# LoadBoard.net
KiCad netlist of a schematic drawn in EAGLE
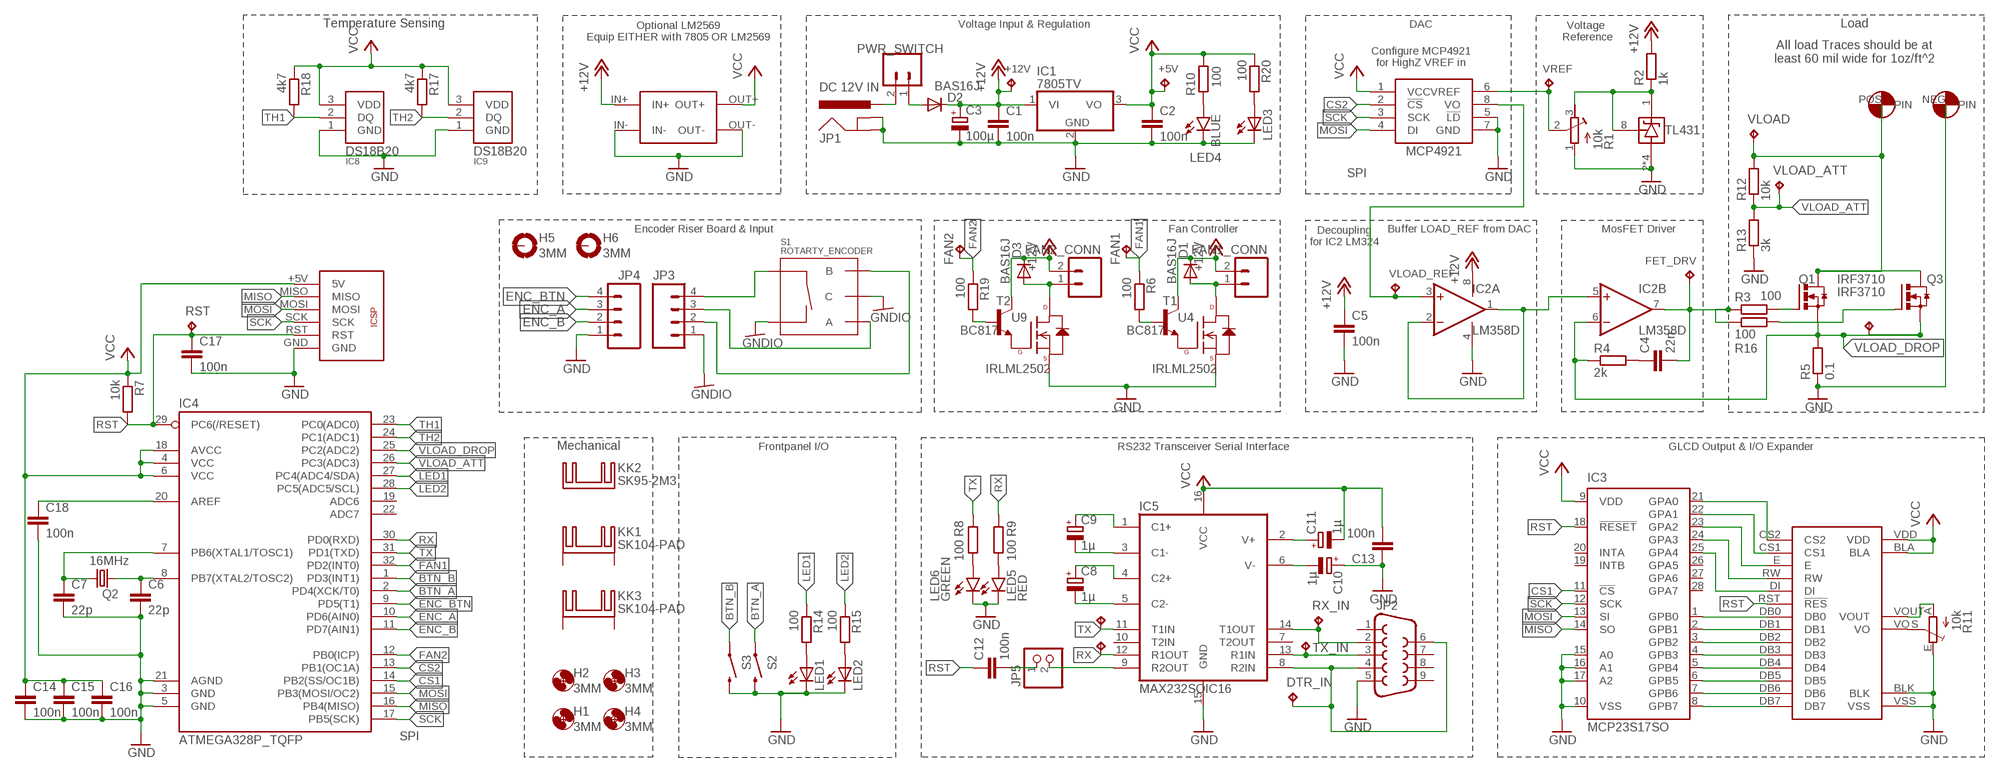
[diagram p0: schematic, sheet 1]

(export (version "E")
  (design (tool "Eeschema 10.0.6"))
  (components
    (comp (ref "+5V")
      (value "TPB1,27")
      (footprint "eagle-import:B1,27")
      (libsource (lib "eagle-import") (part "TPB1,27"))
    )
    (comp (ref "+12V")
      (value "TPB1,27")
      (footprint "eagle-import:B1,27")
      (libsource (lib "eagle-import") (part "TPB1,27"))
    )
    (comp (ref "C1")
      (value "100n")
      (footprint "eagle-import:C1206K")
      (libsource (lib "eagle-import") (part "C-EUC1206K"))
    )
    (comp (ref "C2")
      (value "100n")
      (footprint "eagle-import:C1206K")
      (libsource (lib "eagle-import") (part "C-EUC1206K"))
    )
    (comp (ref "C3")
      (value "100µ")
      (footprint "eagle-import:175TMP-0808")
      (libsource (lib "eagle-import") (part "CPOL-EU175TMP-0808"))
    )
    (comp (ref "C4")
      (value "22n")
      (footprint "eagle-import:C1206")
      (libsource (lib "eagle-import") (part "C-EUC1206"))
    )
    (comp (ref "C5")
      (value "100n")
      (footprint "eagle-import:C1206K")
      (libsource (lib "eagle-import") (part "C-EUC1206K"))
    )
    (comp (ref "C6")
      (value "22p")
      (footprint "eagle-import:C1206K")
      (libsource (lib "eagle-import") (part "C-EUC1206K"))
    )
    (comp (ref "C7")
      (value "22p")
      (footprint "eagle-import:C1206K")
      (libsource (lib "eagle-import") (part "C-EUC1206K"))
    )
    (comp (ref "C8")
      (value "1µ")
      (footprint "eagle-import:153CLV-0405")
      (libsource (lib "eagle-import") (part "CPOL-EU153CLV-0405"))
    )
    (comp (ref "C9")
      (value "1µ")
      (footprint "eagle-import:153CLV-0405")
      (libsource (lib "eagle-import") (part "CPOL-EU153CLV-0405"))
    )
    (comp (ref "C10")
      (value "1µ")
      (footprint "eagle-import:153CLV-0405")
      (libsource (lib "eagle-import") (part "CPOL-EU153CLV-0405"))
    )
    (comp (ref "C11")
      (value "1µ")
      (footprint "eagle-import:153CLV-0405")
      (libsource (lib "eagle-import") (part "CPOL-EU153CLV-0405"))
    )
    (comp (ref "C12")
      (value "100n")
      (footprint "eagle-import:C1206K")
      (libsource (lib "eagle-import") (part "C-EUC1206K"))
    )
    (comp (ref "C13")
      (value "100n")
      (footprint "eagle-import:C1206K")
      (libsource (lib "eagle-import") (part "C-EUC1206K"))
    )
    (comp (ref "C14")
      (value "100n")
      (footprint "eagle-import:C1206K")
      (libsource (lib "eagle-import") (part "C-EUC1206K"))
    )
    (comp (ref "C15")
      (value "100n")
      (footprint "eagle-import:C1206K")
      (libsource (lib "eagle-import") (part "C-EUC1206K"))
    )
    (comp (ref "C16")
      (value "100n")
      (footprint "eagle-import:C1206K")
      (libsource (lib "eagle-import") (part "C-EUC1206K"))
    )
    (comp (ref "C17")
      (value "100n")
      (footprint "eagle-import:C1206K")
      (libsource (lib "eagle-import") (part "C-EUC1206K"))
    )
    (comp (ref "C18")
      (value "100n")
      (footprint "eagle-import:C1206K")
      (libsource (lib "eagle-import") (part "C-EUC1206K"))
    )
    (comp (ref "D1")
      (value "BAS16J")
      (footprint "eagle-import:SOD323-W")
      (libsource (lib "eagle-import") (part "DIODE-SOD323-W"))
    )
    (comp (ref "D2")
      (value "BAS16J")
      (footprint "eagle-import:SOD323-W")
      (libsource (lib "eagle-import") (part "DIODE-SOD323-W"))
    )
    (comp (ref "D3")
      (value "BAS16J")
      (footprint "eagle-import:SOD323-W")
      (libsource (lib "eagle-import") (part "DIODE-SOD323-W"))
    )
    (comp (ref "DTR_IN")
      (value "TPB1,27")
      (footprint "eagle-import:B1,27")
      (libsource (lib "eagle-import") (part "TPB1,27"))
    )
    (comp (ref "FAN1")
      (value "TPB1,27")
      (footprint "eagle-import:B1,27")
      (libsource (lib "eagle-import") (part "TPB1,27"))
    )
    (comp (ref "FAN1_CONN")
      (value "M02POLAR")
      (footprint "eagle-import:MOLEX-1X2")
      (libsource (lib "eagle-import") (part "M02POLAR"))
    )
    (comp (ref "FAN2")
      (value "TPB1,27")
      (footprint "eagle-import:B1,27")
      (libsource (lib "eagle-import") (part "TPB1,27"))
    )
    (comp (ref "FAN2_CONN")
      (value "M02POLAR")
      (footprint "eagle-import:MOLEX-1X2")
      (libsource (lib "eagle-import") (part "M02POLAR"))
    )
    (comp (ref "FET_DRV")
      (value "TPB1,27")
      (footprint "eagle-import:B1,27")
      (libsource (lib "eagle-import") (part "TPB1,27"))
    )
    (comp (ref "H1")
      (value "3MM")
      (footprint "eagle-import:3,0")
      (libsource (lib "eagle-import") (part "MOUNT-HOLE3.0"))
    )
    (comp (ref "H2")
      (value "3MM")
      (footprint "eagle-import:3,0")
      (libsource (lib "eagle-import") (part "MOUNT-HOLE3.0"))
    )
    (comp (ref "H3")
      (value "3MM")
      (footprint "eagle-import:3,0")
      (libsource (lib "eagle-import") (part "MOUNT-HOLE3.0"))
    )
    (comp (ref "H4")
      (value "3MM")
      (footprint "eagle-import:3,0")
      (libsource (lib "eagle-import") (part "MOUNT-HOLE3.0"))
    )
    (comp (ref "H5")
      (value "3MM")
      (footprint "eagle-import:3,0-PAD")
      (libsource (lib "eagle-import") (part "MOUNT-PAD-ROUND3.0"))
    )
    (comp (ref "H6")
      (value "3MM")
      (footprint "eagle-import:3,0-PAD")
      (libsource (lib "eagle-import") (part "MOUNT-PAD-ROUND3.0"))
    )
    (comp (ref "IC1")
      (value "7805TV")
      (footprint "eagle-import:TO220V")
      (libsource (lib "eagle-import") (part "78TV05"))
    )
    (comp (ref "IC2")
      (value "LM358D")
      (footprint "eagle-import:SO08")
      (libsource (lib "eagle-import") (part "LM358D"))
    )
    (comp (ref "IC3")
      (value "MCP23S17SO")
      (footprint "eagle-import:SO28W")
      (fields (field (name "MF") "MICROCHIP") (field (name "MPN") "MCP23S17-E/SO"))
      (libsource (lib "eagle-import") (part "MCP23S17SO"))
    )
    (comp (ref "IC4")
      (value "ATMEGA328P_TQFP")
      (footprint "eagle-import:TQFP32-08")
      (libsource (lib "eagle-import") (part "ATMEGA328P_TQFP"))
    )
    (comp (ref "IC5")
      (value "MAX232SOIC16")
      (footprint "eagle-import:SO016")
      (libsource (lib "eagle-import") (part "MAX232SOIC16"))
    )
    (comp (ref "IC6")
      (value "MCP4921")
      (footprint "eagle-import:SO-8")
      (libsource (lib "eagle-import") (part "MCP4921"))
    )
    (comp (ref "IC7")
      (value "TL431CD")
      (footprint "eagle-import:SO-8")
      (libsource (lib "eagle-import") (part "TL431CD"))
    )
    (comp (ref "IC8")
      (value "DS18B20")
      (footprint "eagle-import:TO-92")
      (libsource (lib "eagle-import") (part "DS18B20"))
    )
    (comp (ref "IC9")
      (value "DS18B20")
      (footprint "eagle-import:TO-92")
      (libsource (lib "eagle-import") (part "DS18B20"))
    )
    (comp (ref "JP1")
      (value "DC 12V IN")
      (footprint "eagle-import:POWER_JACK_PTH")
      (libsource (lib "eagle-import") (part "POWER_JACKPTH"))
    )
    (comp (ref "JP2")
      (value "DB9FEMALE")
      (footprint "eagle-import:DB9")
      (libsource (lib "eagle-import") (part "DB9FEMALE"))
    )
    (comp (ref "JP3")
      (value "M04POLAR")
      (footprint "eagle-import:MOLEX-1X4")
      (libsource (lib "eagle-import") (part "M04POLAR"))
    )
    (comp (ref "JP4")
      (value "M04POLAR")
      (footprint "eagle-import:MOLEX-1X4")
      (libsource (lib "eagle-import") (part "M04POLAR"))
    )
    (comp (ref "JP5")
      (value "PINHD-1X2")
      (footprint "eagle-import:1X02")
      (libsource (lib "eagle-import") (part "PINHD-1X2"))
    )
    (comp (ref "KK1")
      (value "SK104-PAD")
      (footprint "eagle-import:SK104-PAD")
      (libsource (lib "eagle-import") (part "SK104-PAD"))
    )
    (comp (ref "KK2")
      (value "SK95-2M3")
      (footprint "eagle-import:SK95-2M3")
      (libsource (lib "eagle-import") (part "SK95-2M3"))
    )
    (comp (ref "KK3")
      (value "SK104-PAD")
      (footprint "eagle-import:SK104-PAD")
      (libsource (lib "eagle-import") (part "SK104-PAD"))
    )
    (comp (ref "LED1")
      (value "LEDB155")
      (footprint "eagle-import:Q62902-B155")
      (libsource (lib "eagle-import") (part "LEDB155"))
    )
    (comp (ref "LED2")
      (value "LEDB155")
      (footprint "eagle-import:Q62902-B155")
      (libsource (lib "eagle-import") (part "LEDB155"))
    )
    (comp (ref "LED3")
      (value "LEDB155")
      (footprint "eagle-import:Q62902-B155")
      (libsource (lib "eagle-import") (part "LEDB155"))
    )
    (comp (ref "LED4")
      (value "BLUE")
      (footprint "eagle-import:LED-0603")
      (libsource (lib "eagle-import") (part "LED0603"))
    )
    (comp (ref "LED5")
      (value "RED")
      (footprint "eagle-import:LED-0603")
      (libsource (lib "eagle-import") (part "LED0603"))
    )
    (comp (ref "LED6")
      (value "GREEN")
      (footprint "eagle-import:LED-0603")
      (libsource (lib "eagle-import") (part "LED0603"))
    )
    (comp (ref "PWR_SWITCH")
      (value "M02POLAR")
      (footprint "eagle-import:MOLEX-1X2")
      (libsource (lib "eagle-import") (part "M02POLAR"))
    )
    (comp (ref "Q1")
      (value "IRF3710")
      (footprint "eagle-import:TO-220-V")
      (libsource (lib "eagle-import") (part "IRFZ44N"))
    )
    (comp (ref "Q2")
      (value "16MHz")
      (footprint "eagle-import:HC49UP")
      (libsource (lib "eagle-import") (part "CRYSTALHC49UP"))
    )
    (comp (ref "Q3")
      (value "IRF3710")
      (footprint "eagle-import:TO-220-V")
      (libsource (lib "eagle-import") (part "IRFZ44N"))
    )
    (comp (ref "R1")
      (value "10k")
      (footprint "eagle-import:RTRIM3296Y")
      (libsource (lib "eagle-import") (part "R-TRIMM3296Y"))
    )
    (comp (ref "R2")
      (value "1k")
      (footprint "eagle-import:M1206")
      (libsource (lib "eagle-import") (part "R-EU_M1206"))
    )
    (comp (ref "R3")
      (value "100")
      (footprint "eagle-import:R1206")
      (libsource (lib "eagle-import") (part "R-EU_R1206"))
    )
    (comp (ref "R4")
      (value "2k")
      (footprint "eagle-import:R1206")
      (libsource (lib "eagle-import") (part "R-EU_R1206"))
    )
    (comp (ref "R5")
      (value "0.1")
      (footprint "eagle-import:VTA52")
      (libsource (lib "eagle-import") (part "R-EU_VTA52"))
    )
    (comp (ref "R6")
      (value "100")
      (footprint "eagle-import:R1206")
      (libsource (lib "eagle-import") (part "R-EU_R1206"))
    )
    (comp (ref "R7")
      (value "10k")
      (footprint "eagle-import:R1206")
      (libsource (lib "eagle-import") (part "R-EU_R1206"))
    )
    (comp (ref "R8")
      (value "100")
      (footprint "eagle-import:R1206")
      (libsource (lib "eagle-import") (part "R-EU_R1206"))
    )
    (comp (ref "R9")
      (value "100")
      (footprint "eagle-import:R1206")
      (libsource (lib "eagle-import") (part "R-EU_R1206"))
    )
    (comp (ref "R10")
      (value "100")
      (footprint "eagle-import:R1206")
      (libsource (lib "eagle-import") (part "R-EU_R1206"))
    )
    (comp (ref "R11")
      (value "10k")
      (footprint "eagle-import:RS3")
      (libsource (lib "eagle-import") (part "TRIM_EU-RS3"))
    )
    (comp (ref "R12")
      (value "10k")
      (footprint "eagle-import:R1206")
      (libsource (lib "eagle-import") (part "R-EU_R1206"))
    )
    (comp (ref "R13")
      (value "3k")
      (footprint "eagle-import:R1206")
      (libsource (lib "eagle-import") (part "R-EU_R1206"))
    )
    (comp (ref "R14")
      (value "100")
      (footprint "eagle-import:R1206")
      (libsource (lib "eagle-import") (part "R-EU_R1206"))
    )
    (comp (ref "R15")
      (value "100")
      (footprint "eagle-import:R1206")
      (libsource (lib "eagle-import") (part "R-EU_R1206"))
    )
    (comp (ref "R16")
      (value "100")
      (footprint "eagle-import:R1206")
      (libsource (lib "eagle-import") (part "R-EU_R1206"))
    )
    (comp (ref "R17")
      (value "4k7")
      (footprint "eagle-import:M1206")
      (libsource (lib "eagle-import") (part "R-EU_M1206"))
    )
    (comp (ref "R18")
      (value "4k7")
      (footprint "eagle-import:M1206")
      (libsource (lib "eagle-import") (part "R-EU_M1206"))
    )
    (comp (ref "R19")
      (value "100")
      (footprint "eagle-import:R1206")
      (libsource (lib "eagle-import") (part "R-EU_R1206"))
    )
    (comp (ref "R20")
      (value "100")
      (footprint "eagle-import:R1206")
      (libsource (lib "eagle-import") (part "R-EU_R1206"))
    )
    (comp (ref "RST")
      (value "TPB1,27")
      (footprint "eagle-import:B1,27")
      (libsource (lib "eagle-import") (part "TPB1,27"))
    )
    (comp (ref "RX")
      (value "TPB1,27")
      (footprint "eagle-import:B1,27")
      (libsource (lib "eagle-import") (part "TPB1,27"))
    )
    (comp (ref "RX_IN")
      (value "TPB1,27")
      (footprint "eagle-import:B1,27")
      (libsource (lib "eagle-import") (part "TPB1,27"))
    )
    (comp (ref "S1")
      (value "ROTARTY_ENCODER")
      (footprint "eagle-import:ROTARY_ENC_PLAIN")
      (libsource (lib "eagle-import") (part "ROTARTY_ENCODER"))
    )
    (comp (ref "S2")
      (value "SWITCH-MOMENTARY-2SIDE_EZ")
      (footprint "eagle-import:TACTILE-PTH-SIDEEZ")
      (libsource (lib "eagle-import") (part "SWITCH-MOMENTARY-2SIDE_EZ"))
    )
    (comp (ref "S3")
      (value "SWITCH-MOMENTARY-2SIDE_EZ")
      (footprint "eagle-import:TACTILE-PTH-SIDEEZ")
      (libsource (lib "eagle-import") (part "SWITCH-MOMENTARY-2SIDE_EZ"))
    )
    (comp (ref "T1")
      (value "BC817")
      (footprint "eagle-import:SOT23-BEC")
      (libsource (lib "eagle-import") (part "-NPN-SOT23-BECBC817"))
    )
    (comp (ref "T2")
      (value "BC817")
      (footprint "eagle-import:SOT23-BEC")
      (libsource (lib "eagle-import") (part "-NPN-SOT23-BECBC817"))
    )
    (comp (ref "TX")
      (value "TPB1,27")
      (footprint "eagle-import:B1,27")
      (libsource (lib "eagle-import") (part "TPB1,27"))
    )
    (comp (ref "TX_IN")
      (value "TPB1,27")
      (footprint "eagle-import:B1,27")
      (libsource (lib "eagle-import") (part "TPB1,27"))
    )
    (comp (ref "U$3")
      (value "CON-2-HIGAMP")
      (footprint "eagle-import:CON-HIGHAMP-0.3_")
      (libsource (lib "eagle-import") (part "CON-2-HIGAMP"))
    )
    (comp (ref "U$5")
      (value "ICSPTHROUGHHOLE")
      (footprint "eagle-import:ICSP-THROUGHHOLE")
      (libsource (lib "eagle-import") (part "ICSPTHROUGHHOLE"))
    )
    (comp (ref "U$6")
      (value "KS0108-GLCDS6B0108")
      (footprint "eagle-import:KS0108-S6B0108-GLCD")
      (libsource (lib "eagle-import") (part "KS0108-GLCDS6B0108"))
    )
    (comp (ref "U$10")
      (value "LM2569NO_OUTLINE")
      (footprint "eagle-import:LM2596_NO_OUTLINE")
      (libsource (lib "eagle-import") (part "LM2569NO_OUTLINE"))
    )
    (comp (ref "U4")
      (value "IRLML2502")
      (footprint "eagle-import:SOT23-3")
      (libsource (lib "eagle-import") (part "N-CHANNEL-MOSFET-BSS138"))
    )
    (comp (ref "U9")
      (value "IRLML2502")
      (footprint "eagle-import:SOT23-3")
      (libsource (lib "eagle-import") (part "N-CHANNEL-MOSFET-BSS138"))
    )
    (comp (ref "VLOAD")
      (value "TPB1,27")
      (footprint "eagle-import:B1,27")
      (libsource (lib "eagle-import") (part "TPB1,27"))
    )
    (comp (ref "VLOAD_ATT")
      (value "TPB1,27")
      (footprint "eagle-import:B1,27")
      (libsource (lib "eagle-import") (part "TPB1,27"))
    )
    (comp (ref "VLOAD_DROP")
      (value "TPB1,27")
      (footprint "eagle-import:B1,27")
      (libsource (lib "eagle-import") (part "TPB1,27"))
    )
    (comp (ref "VLOAD_REF")
      (value "TPB1,27")
      (footprint "eagle-import:B1,27")
      (libsource (lib "eagle-import") (part "TPB1,27"))
    )
    (comp (ref "VREF")
      (value "TPB1,27")
      (footprint "eagle-import:B1,27")
      (libsource (lib "eagle-import") (part "TPB1,27"))
    )
  )
  (nets
    (net (code "1") (name "+12V") (class "Default")
      (node (ref "+12V") (pin "TP") (pinfunction "TP_TP") (pintype "input"))
      (node (ref "C1") (pin "1") (pinfunction "1_1") (pintype "passive"))
      (node (ref "C3") (pin "+") (pinfunction "+_+") (pintype "passive"))
      (node (ref "C5") (pin "1") (pinfunction "1_1") (pintype "passive"))
      (node (ref "D1") (pin "C") (pinfunction "C_C") (pintype "passive"))
      (node (ref "D2") (pin "C") (pinfunction "C_C") (pintype "passive"))
      (node (ref "D3") (pin "C") (pinfunction "C_C") (pintype "passive"))
      (node (ref "FAN1_CONN") (pin "2") (pinfunction "2_2") (pintype "passive"))
      (node (ref "FAN2_CONN") (pin "2") (pinfunction "2_2") (pintype "passive"))
      (node (ref "IC1") (pin "1") (pinfunction "VI_1") (pintype "input"))
      (node (ref "IC2") (pin "8") (pinfunction "V+_8") (pintype "power_in"))
      (node (ref "R2") (pin "2") (pinfunction "2_2") (pintype "passive"))
      (node (ref "T1") (pin "C") (pinfunction "C_C") (pintype "passive"))
      (node (ref "T2") (pin "C") (pinfunction "C_C") (pintype "passive"))
      (node (ref "U$10") (pin "IN+") (pinfunction "IN+_IN+") (pintype "bidirectional"))
    )
    (net (code "2") (name "BTN_A") (class "Default")
      (node (ref "IC4") (pin "2") (pinfunction "PD4(XCK/T0)_2") (pintype "bidirectional"))
      (node (ref "S2") (pin "1") (pinfunction "1_1") (pintype "passive"))
    )
    (net (code "3") (name "BTN_B") (class "Default")
      (node (ref "IC4") (pin "1") (pinfunction "PD3(INT1)_1") (pintype "bidirectional"))
      (node (ref "S3") (pin "1") (pinfunction "1_1") (pintype "passive"))
    )
    (net (code "4") (name "CS1") (class "Default")
      (node (ref "IC3") (pin "11") (pinfunction "~{CS}_11") (pintype "input"))
      (node (ref "IC4") (pin "14") (pinfunction "PB2(SS/OC1B)_14") (pintype "bidirectional"))
    )
    (net (code "5") (name "CS2") (class "Default")
      (node (ref "IC4") (pin "13") (pinfunction "PB1(OC1A)_13") (pintype "bidirectional"))
      (node (ref "IC6") (pin "2") (pinfunction "~{CS}_2") (pintype "bidirectional"))
    )
    (net (code "6") (name "ENC_A") (class "Default")
      (node (ref "IC4") (pin "10") (pinfunction "PD6(AIN0)_10") (pintype "bidirectional"))
      (node (ref "JP4") (pin "3") (pinfunction "3_3") (pintype "passive"))
    )
    (net (code "7") (name "ENC_B") (class "Default")
      (node (ref "IC4") (pin "11") (pinfunction "PD7(AIN1)_11") (pintype "bidirectional"))
      (node (ref "JP4") (pin "2") (pinfunction "2_2") (pintype "passive"))
    )
    (net (code "8") (name "ENC_BTN") (class "Default")
      (node (ref "IC4") (pin "9") (pinfunction "PD5(T1)_9") (pintype "bidirectional"))
      (node (ref "JP4") (pin "4") (pinfunction "4_4") (pintype "passive"))
    )
    (net (code "9") (name "FAN1") (class "Default")
      (node (ref "FAN1") (pin "TP") (pinfunction "TP_TP") (pintype "input"))
      (node (ref "IC4") (pin "32") (pinfunction "PD2(INT0)_32") (pintype "bidirectional"))
      (node (ref "R6") (pin "1") (pinfunction "1_1") (pintype "passive"))
    )
    (net (code "10") (name "FAN2") (class "Default")
      (node (ref "FAN2") (pin "TP") (pinfunction "TP_TP") (pintype "input"))
      (node (ref "IC4") (pin "12") (pinfunction "PB0(ICP)_12") (pintype "bidirectional"))
      (node (ref "R19") (pin "1") (pinfunction "1_1") (pintype "passive"))
    )
    (net (code "11") (name "GND") (class "Default")
      (node (ref "C1") (pin "2") (pinfunction "2_2") (pintype "passive"))
      (node (ref "C10") (pin "+") (pinfunction "+_+") (pintype "passive"))
      (node (ref "C13") (pin "1") (pinfunction "1_1") (pintype "passive"))
      (node (ref "C14") (pin "2") (pinfunction "2_2") (pintype "passive"))
      (node (ref "C15") (pin "2") (pinfunction "2_2") (pintype "passive"))
      (node (ref "C16") (pin "2") (pinfunction "2_2") (pintype "passive"))
      (node (ref "C17") (pin "2") (pinfunction "2_2") (pintype "passive"))
      (node (ref "C18") (pin "2") (pinfunction "2_2") (pintype "passive"))
      (node (ref "C2") (pin "2") (pinfunction "2_2") (pintype "passive"))
      (node (ref "C3") (pin "-") (pinfunction "-_-") (pintype "passive"))
      (node (ref "C5") (pin "2") (pinfunction "2_2") (pintype "passive"))
      (node (ref "C6") (pin "2") (pinfunction "2_2") (pintype "passive"))
      (node (ref "C7") (pin "2") (pinfunction "2_2") (pintype "passive"))
      (node (ref "IC1") (pin "2") (pinfunction "GND_2") (pintype "passive"))
      (node (ref "IC2") (pin "4") (pinfunction "V-_4") (pintype "power_in"))
      (node (ref "IC3") (pin "10") (pinfunction "VSS_10") (pintype "power_in"))
      (node (ref "IC3") (pin "15") (pinfunction "A0_15") (pintype "input"))
      (node (ref "IC3") (pin "16") (pinfunction "A1_16") (pintype "input"))
      (node (ref "IC3") (pin "17") (pinfunction "A2_17") (pintype "input"))
      (node (ref "IC4") (pin "21") (pinfunction "AGND_21") (pintype "bidirectional"))
      (node (ref "IC4") (pin "3") (pinfunction "GND_3") (pintype "bidirectional"))
      (node (ref "IC4") (pin "5") (pinfunction "GND_5") (pintype "bidirectional"))
      (node (ref "IC5") (pin "15") (pinfunction "GND_15") (pintype "bidirectional"))
      (node (ref "IC6") (pin "5") (pinfunction "~{LD}_5") (pintype "input"))
      (node (ref "IC6") (pin "7") (pinfunction "GND_7") (pintype "power_in"))
      (node (ref "IC7") (pin "2") (pinfunction "ANODE_2") (pintype "passive"))
      (node (ref "IC7") (pin "3") (pinfunction "ANODE_3") (pintype "passive"))
      (node (ref "IC7") (pin "6") (pinfunction "ANODE_6") (pintype "passive"))
      (node (ref "IC7") (pin "7") (pinfunction "ANODE_7") (pintype "passive"))
      (node (ref "IC8") (pin "1") (pinfunction "GND_1") (pintype "power_in"))
      (node (ref "IC9") (pin "1") (pinfunction "GND_1") (pintype "power_in"))
      (node (ref "JP1") (pin "GND") (pinfunction "GND_GND") (pintype "bidirectional"))
      (node (ref "JP1") (pin "GNDBREAK") (pinfunction "GNDBREAK_GNDBREAK") (pintype "bidirectional"))
      (node (ref "JP2") (pin "5") (pinfunction "5_5") (pintype "passive"))
      (node (ref "JP4") (pin "1") (pinfunction "1_1") (pintype "passive"))
      (node (ref "LED1") (pin "K") (pinfunction "C_K") (pintype "passive"))
      (node (ref "LED2") (pin "K") (pinfunction "C_K") (pintype "passive"))
      (node (ref "LED3") (pin "K") (pinfunction "C_K") (pintype "passive"))
      (node (ref "LED4") (pin "C") (pinfunction "C_C") (pintype "passive"))
      (node (ref "LED5") (pin "C") (pinfunction "C_C") (pintype "passive"))
      (node (ref "LED6") (pin "C") (pinfunction "C_C") (pintype "passive"))
      (node (ref "R1") (pin "1") (pinfunction "A_1") (pintype "passive"))
      (node (ref "R11") (pin "E") (pinfunction "E_E") (pintype "passive"))
      (node (ref "R13") (pin "1") (pinfunction "1_1") (pintype "passive"))
      (node (ref "R5") (pin "1") (pinfunction "1_1") (pintype "passive"))
      (node (ref "S2") (pin "2") (pinfunction "2_2") (pintype "passive"))
      (node (ref "S3") (pin "2") (pinfunction "2_2") (pintype "passive"))
      (node (ref "U$10") (pin "IN-") (pinfunction "IN-_IN-") (pintype "bidirectional"))
      (node (ref "U$10") (pin "OUT-") (pinfunction "OUT-_OUT-") (pintype "bidirectional"))
      (node (ref "U$3") (pin "NEG") (pinfunction "PIN_NEG") (pintype "bidirectional"))
      (node (ref "U$5") (pin "GND") (pinfunction "GND_GND") (pintype "bidirectional"))
      (node (ref "U$6") (pin "BLK") (pinfunction "BLK_BLK") (pintype "bidirectional"))
      (node (ref "U$6") (pin "VSS") (pinfunction "VSS_VSS") (pintype "bidirectional"))
      (node (ref "U4") (pin "2") (pinfunction "S_2") (pintype "passive"))
      (node (ref "U9") (pin "2") (pinfunction "S_2") (pintype "passive"))
    )
    (net (code "12") (name "GNDIO") (class "Default")
      (node (ref "JP3") (pin "1") (pinfunction "1_1") (pintype "passive"))
      (node (ref "S1") (pin "C") (pinfunction "C_C") (pintype "bidirectional"))
      (node (ref "S1") (pin "SW-") (pinfunction "SW-_SW-") (pintype "bidirectional"))
    )
    (net (code "13") (name "LED1") (class "Default")
      (node (ref "IC4") (pin "27") (pinfunction "PC4(ADC4/SDA)_27") (pintype "bidirectional"))
      (node (ref "R14") (pin "1") (pinfunction "1_1") (pintype "passive"))
    )
    (net (code "14") (name "LED2") (class "Default")
      (node (ref "IC4") (pin "28") (pinfunction "PC5(ADC5/SCL)_28") (pintype "bidirectional"))
      (node (ref "R15") (pin "1") (pinfunction "1_1") (pintype "passive"))
    )
    (net (code "15") (name "MISO") (class "Default")
      (node (ref "IC3") (pin "14") (pinfunction "SO_14") (pintype "output"))
      (node (ref "IC4") (pin "16") (pinfunction "PB4(MISO)_16") (pintype "bidirectional"))
      (node (ref "U$5") (pin "MISO") (pinfunction "MISO_MISO") (pintype "bidirectional"))
    )
    (net (code "16") (name "MOSI") (class "Default")
      (node (ref "IC3") (pin "13") (pinfunction "SI_13") (pintype "input"))
      (node (ref "IC4") (pin "15") (pinfunction "PB3(MOSI/OC2)_15") (pintype "bidirectional"))
      (node (ref "IC6") (pin "4") (pinfunction "DI_4") (pintype "bidirectional"))
      (node (ref "U$5") (pin "MOSI") (pinfunction "MOSI_MOSI") (pintype "bidirectional"))
    )
    (net (code "17") (name "Net-(C4-Pad1)") (class "Default")
      (node (ref "C4") (pin "1") (pinfunction "1_1") (pintype "passive"))
      (node (ref "R4") (pin "2") (pinfunction "2_2") (pintype "passive"))
    )
    (net (code "18") (name "Net-(C12-Pad2)") (class "Default")
      (node (ref "C12") (pin "2") (pinfunction "2_2") (pintype "passive"))
      (node (ref "JP5") (pin "1") (pinfunction "1_1") (pintype "passive"))
    )
    (net (code "19") (name "Net-(D2-PadA)") (class "Default")
      (node (ref "D2") (pin "A") (pinfunction "A_A") (pintype "passive"))
      (node (ref "PWR_SWITCH") (pin "1") (pinfunction "1_1") (pintype "passive"))
    )
    (net (code "20") (name "Net-(IC2A-+IN)") (class "Default")
      (node (ref "IC2") (pin "3") (pinfunction "+IN_3") (pintype "input"))
      (node (ref "IC6") (pin "8") (pinfunction "VO_8") (pintype "output"))
      (node (ref "VLOAD_REF") (pin "TP") (pinfunction "TP_TP") (pintype "input"))
    )
    (net (code "21") (name "Net-(IC2A--IN)") (class "Default")
      (node (ref "IC2") (pin "1") (pinfunction "OUT_1") (pintype "output"))
      (node (ref "IC2") (pin "2") (pinfunction "-IN_2") (pintype "input"))
      (node (ref "IC2") (pin "5") (pinfunction "+IN_5") (pintype "input"))
    )
    (net (code "22") (name "Net-(IC2B-OUT)") (class "Default")
      (node (ref "C4") (pin "2") (pinfunction "2_2") (pintype "passive"))
      (node (ref "FET_DRV") (pin "TP") (pinfunction "TP_TP") (pintype "input"))
      (node (ref "IC2") (pin "7") (pinfunction "OUT_7") (pintype "output"))
      (node (ref "R16") (pin "1") (pinfunction "1_1") (pintype "passive"))
      (node (ref "R3") (pin "1") (pinfunction "1_1") (pintype "passive"))
    )
    (net (code "23") (name "Net-(IC3-GPA0)") (class "Default")
      (node (ref "IC3") (pin "21") (pinfunction "GPA0_21") (pintype "bidirectional"))
      (node (ref "U$6") (pin "CS2") (pinfunction "CS2_CS2") (pintype "bidirectional"))
    )
    (net (code "24") (name "Net-(IC3-GPA1)") (class "Default")
      (node (ref "IC3") (pin "22") (pinfunction "GPA1_22") (pintype "bidirectional"))
      (node (ref "U$6") (pin "CS1") (pinfunction "CS1_CS1") (pintype "bidirectional"))
    )
    (net (code "25") (name "Net-(IC3-GPA2)") (class "Default")
      (node (ref "IC3") (pin "23") (pinfunction "GPA2_23") (pintype "bidirectional"))
      (node (ref "U$6") (pin "E") (pinfunction "E_E") (pintype "bidirectional"))
    )
    (net (code "26") (name "Net-(IC3-GPA3)") (class "Default")
      (node (ref "IC3") (pin "24") (pinfunction "GPA3_24") (pintype "bidirectional"))
      (node (ref "U$6") (pin "RW") (pinfunction "RW_RW") (pintype "bidirectional"))
    )
    (net (code "27") (name "Net-(IC3-GPA4)") (class "Default")
      (node (ref "IC3") (pin "25") (pinfunction "GPA4_25") (pintype "bidirectional"))
      (node (ref "U$6") (pin "DI") (pinfunction "DI_DI") (pintype "bidirectional"))
    )
    (net (code "28") (name "Net-(IC3-GPB0)") (class "Default")
      (node (ref "IC3") (pin "1") (pinfunction "GPB0_1") (pintype "bidirectional"))
      (node (ref "U$6") (pin "DB0") (pinfunction "DB0_DB0") (pintype "bidirectional"))
    )
    (net (code "29") (name "Net-(IC3-GPB1)") (class "Default")
      (node (ref "IC3") (pin "2") (pinfunction "GPB1_2") (pintype "bidirectional"))
      (node (ref "U$6") (pin "DB1") (pinfunction "DB1_DB1") (pintype "bidirectional"))
    )
    (net (code "30") (name "Net-(IC3-GPB2)") (class "Default")
      (node (ref "IC3") (pin "3") (pinfunction "GPB2_3") (pintype "bidirectional"))
      (node (ref "U$6") (pin "DB2") (pinfunction "DB2_DB2") (pintype "bidirectional"))
    )
    (net (code "31") (name "Net-(IC3-GPB3)") (class "Default")
      (node (ref "IC3") (pin "4") (pinfunction "GPB3_4") (pintype "bidirectional"))
      (node (ref "U$6") (pin "DB3") (pinfunction "DB3_DB3") (pintype "bidirectional"))
    )
    (net (code "32") (name "Net-(IC3-GPB4)") (class "Default")
      (node (ref "IC3") (pin "5") (pinfunction "GPB4_5") (pintype "bidirectional"))
      (node (ref "U$6") (pin "DB4") (pinfunction "DB4_DB4") (pintype "bidirectional"))
    )
    (net (code "33") (name "Net-(IC3-GPB5)") (class "Default")
      (node (ref "IC3") (pin "6") (pinfunction "GPB5_6") (pintype "bidirectional"))
      (node (ref "U$6") (pin "DB5") (pinfunction "DB5_DB5") (pintype "bidirectional"))
    )
    (net (code "34") (name "Net-(IC3-GPB6)") (class "Default")
      (node (ref "IC3") (pin "7") (pinfunction "GPB6_7") (pintype "bidirectional"))
      (node (ref "U$6") (pin "DB6") (pinfunction "DB6_DB6") (pintype "bidirectional"))
    )
    (net (code "35") (name "Net-(IC3-GPB7)") (class "Default")
      (node (ref "IC3") (pin "8") (pinfunction "GPB7_8") (pintype "bidirectional"))
      (node (ref "U$6") (pin "DB7") (pinfunction "DB7_DB7") (pintype "bidirectional"))
    )
    (net (code "36") (name "Net-(IC4-AREF)") (class "Default")
      (node (ref "C18") (pin "1") (pinfunction "1_1") (pintype "passive"))
      (node (ref "IC4") (pin "20") (pinfunction "AREF_20") (pintype "bidirectional"))
    )
    (net (code "37") (name "Net-(IC4-PB6(XTAL1{slash}TOSC1))") (class "Default")
      (node (ref "C7") (pin "1") (pinfunction "1_1") (pintype "passive"))
      (node (ref "IC4") (pin "7") (pinfunction "PB6(XTAL1/TOSC1)_7") (pintype "bidirectional"))
      (node (ref "Q2") (pin "1") (pinfunction "1_1") (pintype "passive"))
    )
    (net (code "38") (name "Net-(IC4-PB7(XTAL2{slash}TOSC2))") (class "Default")
      (node (ref "C6") (pin "1") (pinfunction "1_1") (pintype "passive"))
      (node (ref "IC4") (pin "8") (pinfunction "PB7(XTAL2/TOSC2)_8") (pintype "bidirectional"))
      (node (ref "Q2") (pin "2") (pinfunction "2_2") (pintype "passive"))
    )
    (net (code "39") (name "Net-(IC5-C1+)") (class "Default")
      (node (ref "C9") (pin "+") (pinfunction "+_+") (pintype "passive"))
      (node (ref "IC5") (pin "1") (pinfunction "C1+_1") (pintype "bidirectional"))
    )
    (net (code "40") (name "Net-(IC5-C1-)") (class "Default")
      (node (ref "C9") (pin "-") (pinfunction "-_-") (pintype "passive"))
      (node (ref "IC5") (pin "3") (pinfunction "C1-_3") (pintype "bidirectional"))
    )
    (net (code "41") (name "Net-(IC5-C2+)") (class "Default")
      (node (ref "C8") (pin "+") (pinfunction "+_+") (pintype "passive"))
      (node (ref "IC5") (pin "4") (pinfunction "C2+_4") (pintype "bidirectional"))
    )
    (net (code "42") (name "Net-(IC5-C2-)") (class "Default")
      (node (ref "C8") (pin "-") (pinfunction "-_-") (pintype "passive"))
      (node (ref "IC5") (pin "5") (pinfunction "C2-_5") (pintype "bidirectional"))
    )
    (net (code "43") (name "Net-(IC5-R1IN)") (class "Default")
      (node (ref "IC5") (pin "13") (pinfunction "R1IN_13") (pintype "input"))
      (node (ref "JP2") (pin "3") (pinfunction "3_3") (pintype "passive"))
      (node (ref "TX_IN") (pin "TP") (pinfunction "TP_TP") (pintype "input"))
    )
    (net (code "44") (name "Net-(IC5-R2IN)") (class "Default")
      (node (ref "DTR_IN") (pin "TP") (pinfunction "TP_TP") (pintype "input"))
      (node (ref "IC5") (pin "8") (pinfunction "R2IN_8") (pintype "input"))
      (node (ref "JP2") (pin "4") (pinfunction "4_4") (pintype "passive"))
      (node (ref "JP2") (pin "6") (pinfunction "6_6") (pintype "passive"))
    )
    (net (code "45") (name "Net-(IC5-R2OUT)") (class "Default")
      (node (ref "IC5") (pin "9") (pinfunction "R2OUT_9") (pintype "output"))
      (node (ref "JP5") (pin "2") (pinfunction "2_2") (pintype "passive"))
    )
    (net (code "46") (name "Net-(IC5-T1OUT)") (class "Default")
      (node (ref "IC5") (pin "14") (pinfunction "T1OUT_14") (pintype "output"))
      (node (ref "JP2") (pin "2") (pinfunction "2_2") (pintype "passive"))
      (node (ref "RX_IN") (pin "TP") (pinfunction "TP_TP") (pintype "input"))
    )
    (net (code "47") (name "Net-(IC5-V+)") (class "Default")
      (node (ref "C11") (pin "+") (pinfunction "+_+") (pintype "passive"))
      (node (ref "IC5") (pin "2") (pinfunction "V+_2") (pintype "bidirectional"))
    )
    (net (code "48") (name "Net-(IC5-V-)") (class "Default")
      (node (ref "C10") (pin "-") (pinfunction "-_-") (pintype "passive"))
      (node (ref "IC5") (pin "6") (pinfunction "V-_6") (pintype "bidirectional"))
    )
    (net (code "49") (name "Net-(IC6-VREF)") (class "Default")
      (node (ref "IC6") (pin "6") (pinfunction "VREF_6") (pintype "input"))
      (node (ref "R1") (pin "2") (pinfunction "S_2") (pintype "passive"))
      (node (ref "VREF") (pin "TP") (pinfunction "TP_TP") (pintype "input"))
    )
    (net (code "50") (name "Net-(IC7-CATHODE)") (class "Default")
      (node (ref "IC7") (pin "1") (pinfunction "CATHODE_1") (pintype "passive"))
      (node (ref "IC7") (pin "8") (pinfunction "REF_8") (pintype "passive"))
      (node (ref "R1") (pin "3") (pinfunction "E_3") (pintype "passive"))
      (node (ref "R2") (pin "1") (pinfunction "1_1") (pintype "passive"))
    )
    (net (code "51") (name "Net-(JP1-PadPWR)") (class "Default")
      (node (ref "JP1") (pin "PWR") (pinfunction "PWR_PWR") (pintype "bidirectional"))
      (node (ref "PWR_SWITCH") (pin "2") (pinfunction "2_2") (pintype "passive"))
    )
    (net (code "52") (name "Net-(JP3-Pad2)") (class "Default")
      (node (ref "JP3") (pin "2") (pinfunction "2_2") (pintype "passive"))
      (node (ref "S1") (pin "B") (pinfunction "B_B") (pintype "bidirectional"))
    )
    (net (code "53") (name "Net-(JP3-Pad3)") (class "Default")
      (node (ref "JP3") (pin "3") (pinfunction "3_3") (pintype "passive"))
      (node (ref "S1") (pin "A") (pinfunction "A_A") (pintype "bidirectional"))
    )
    (net (code "54") (name "Net-(JP3-Pad4)") (class "Default")
      (node (ref "JP3") (pin "4") (pinfunction "4_4") (pintype "passive"))
      (node (ref "S1") (pin "SW+") (pinfunction "SW+_SW+") (pintype "bidirectional"))
    )
    (net (code "55") (name "Net-(LED1-PadA)") (class "Default")
      (node (ref "LED1") (pin "A") (pinfunction "A_A") (pintype "passive"))
      (node (ref "R14") (pin "2") (pinfunction "2_2") (pintype "passive"))
    )
    (net (code "56") (name "Net-(LED2-PadA)") (class "Default")
      (node (ref "LED2") (pin "A") (pinfunction "A_A") (pintype "passive"))
      (node (ref "R15") (pin "2") (pinfunction "2_2") (pintype "passive"))
    )
    (net (code "57") (name "Net-(LED3-PadA)") (class "Default")
      (node (ref "LED3") (pin "A") (pinfunction "A_A") (pintype "passive"))
      (node (ref "R20") (pin "2") (pinfunction "2_2") (pintype "passive"))
    )
    (net (code "58") (name "Net-(LED4-PadA)") (class "Default")
      (node (ref "LED4") (pin "A") (pinfunction "A_A") (pintype "passive"))
      (node (ref "R10") (pin "2") (pinfunction "2_2") (pintype "passive"))
    )
    (net (code "59") (name "Net-(LED5-PadA)") (class "Default")
      (node (ref "LED5") (pin "A") (pinfunction "A_A") (pintype "passive"))
      (node (ref "R9") (pin "2") (pinfunction "2_2") (pintype "passive"))
    )
    (net (code "60") (name "Net-(LED6-PadA)") (class "Default")
      (node (ref "LED6") (pin "A") (pinfunction "A_A") (pintype "passive"))
      (node (ref "R8") (pin "2") (pinfunction "2_2") (pintype "passive"))
    )
    (net (code "61") (name "Net-(Q1-D)") (class "Default")
      (node (ref "Q1") (pin "2") (pinfunction "D_2") (pintype "passive"))
      (node (ref "Q3") (pin "2") (pinfunction "D_2") (pintype "passive"))
      (node (ref "R12") (pin "2") (pinfunction "2_2") (pintype "passive"))
      (node (ref "U$3") (pin "POS") (pinfunction "PIN_POS") (pintype "bidirectional"))
      (node (ref "VLOAD") (pin "TP") (pinfunction "TP_TP") (pintype "input"))
    )
    (net (code "62") (name "Net-(Q1-G)") (class "Default")
      (node (ref "Q1") (pin "1") (pinfunction "G_1") (pintype "passive"))
      (node (ref "R3") (pin "2") (pinfunction "2_2") (pintype "passive"))
    )
    (net (code "63") (name "Net-(Q3-G)") (class "Default")
      (node (ref "Q3") (pin "1") (pinfunction "G_1") (pintype "passive"))
      (node (ref "R16") (pin "2") (pinfunction "2_2") (pintype "passive"))
    )
    (net (code "64") (name "Net-(R6-Pad2)") (class "Default")
      (node (ref "R6") (pin "2") (pinfunction "2_2") (pintype "passive"))
      (node (ref "T1") (pin "B") (pinfunction "B_B") (pintype "passive"))
    )
    (net (code "65") (name "Net-(R11-PadA)") (class "Default")
      (node (ref "R11") (pin "A") (pinfunction "A_A") (pintype "passive"))
      (node (ref "U$6") (pin "VOUT") (pinfunction "VOUT_VOUT") (pintype "bidirectional"))
    )
    (net (code "66") (name "Net-(R11-PadS)") (class "Default")
      (node (ref "R11") (pin "S") (pinfunction "S_S") (pintype "passive"))
      (node (ref "U$6") (pin "VO") (pinfunction "VO_VO") (pintype "bidirectional"))
    )
    (net (code "67") (name "Net-(R19-Pad2)") (class "Default")
      (node (ref "R19") (pin "2") (pinfunction "2_2") (pintype "passive"))
      (node (ref "T2") (pin "B") (pinfunction "B_B") (pintype "passive"))
    )
    (net (code "68") (name "Net-(U4-D)") (class "Default")
      (node (ref "D1") (pin "A") (pinfunction "A_A") (pintype "passive"))
      (node (ref "FAN1_CONN") (pin "1") (pinfunction "1_1") (pintype "passive"))
      (node (ref "U4") (pin "3") (pinfunction "D_3") (pintype "passive"))
    )
    (net (code "69") (name "Net-(U4-G)") (class "Default")
      (node (ref "T1") (pin "E") (pinfunction "E_E") (pintype "passive"))
      (node (ref "U4") (pin "1") (pinfunction "G_1") (pintype "passive"))
    )
    (net (code "70") (name "Net-(U9-D)") (class "Default")
      (node (ref "D3") (pin "A") (pinfunction "A_A") (pintype "passive"))
      (node (ref "FAN2_CONN") (pin "1") (pinfunction "1_1") (pintype "passive"))
      (node (ref "U9") (pin "3") (pinfunction "D_3") (pintype "passive"))
    )
    (net (code "71") (name "Net-(U9-G)") (class "Default")
      (node (ref "T2") (pin "E") (pinfunction "E_E") (pintype "passive"))
      (node (ref "U9") (pin "1") (pinfunction "G_1") (pintype "passive"))
    )
    (net (code "72") (name "RST") (class "Default")
      (node (ref "C12") (pin "1") (pinfunction "1_1") (pintype "passive"))
      (node (ref "C17") (pin "1") (pinfunction "1_1") (pintype "passive"))
      (node (ref "IC3") (pin "18") (pinfunction "~{RESET}_18") (pintype "input"))
      (node (ref "IC4") (pin "29") (pinfunction "PC6(/RESET)_29") (pintype "bidirectional"))
      (node (ref "R7") (pin "2") (pinfunction "2_2") (pintype "passive"))
      (node (ref "RST") (pin "TP") (pinfunction "TP_TP") (pintype "input"))
      (node (ref "U$5") (pin "RST") (pinfunction "RST_RST") (pintype "bidirectional"))
      (node (ref "U$6") (pin "RST") (pinfunction "~{RES}_RST") (pintype "bidirectional"))
    )
    (net (code "73") (name "RX") (class "Default")
      (node (ref "IC4") (pin "30") (pinfunction "PD0(RXD)_30") (pintype "bidirectional"))
      (node (ref "IC5") (pin "12") (pinfunction "R1OUT_12") (pintype "output"))
      (node (ref "R9") (pin "1") (pinfunction "1_1") (pintype "passive"))
      (node (ref "RX") (pin "TP") (pinfunction "TP_TP") (pintype "input"))
    )
    (net (code "74") (name "SCK") (class "Default")
      (node (ref "IC3") (pin "12") (pinfunction "SCK_12") (pintype "input"))
      (node (ref "IC4") (pin "17") (pinfunction "PB5(SCK)_17") (pintype "bidirectional"))
      (node (ref "IC6") (pin "3") (pinfunction "SCK_3") (pintype "bidirectional"))
      (node (ref "U$5") (pin "SCK") (pinfunction "SCK_SCK") (pintype "bidirectional"))
    )
    (net (code "75") (name "TH1") (class "Default")
      (node (ref "IC4") (pin "23") (pinfunction "PC0(ADC0)_23") (pintype "bidirectional"))
      (node (ref "IC8") (pin "2") (pinfunction "DQ_2") (pintype "bidirectional"))
      (node (ref "R18") (pin "2") (pinfunction "2_2") (pintype "passive"))
    )
    (net (code "76") (name "TH2") (class "Default")
      (node (ref "IC4") (pin "24") (pinfunction "PC1(ADC1)_24") (pintype "bidirectional"))
      (node (ref "IC9") (pin "2") (pinfunction "DQ_2") (pintype "bidirectional"))
      (node (ref "R17") (pin "2") (pinfunction "2_2") (pintype "passive"))
    )
    (net (code "77") (name "TX") (class "Default")
      (node (ref "IC4") (pin "31") (pinfunction "PD1(TXD)_31") (pintype "bidirectional"))
      (node (ref "IC5") (pin "11") (pinfunction "T1IN_11") (pintype "input"))
      (node (ref "R8") (pin "1") (pinfunction "1_1") (pintype "passive"))
      (node (ref "TX") (pin "TP") (pinfunction "TP_TP") (pintype "input"))
    )
    (net (code "78") (name "VCC") (class "Default")
      (node (ref "+5V") (pin "TP") (pinfunction "TP_TP") (pintype "input"))
      (node (ref "C11") (pin "-") (pinfunction "-_-") (pintype "passive"))
      (node (ref "C13") (pin "2") (pinfunction "2_2") (pintype "passive"))
      (node (ref "C14") (pin "1") (pinfunction "1_1") (pintype "passive"))
      (node (ref "C15") (pin "1") (pinfunction "1_1") (pintype "passive"))
      (node (ref "C16") (pin "1") (pinfunction "1_1") (pintype "passive"))
      (node (ref "C2") (pin "1") (pinfunction "1_1") (pintype "passive"))
      (node (ref "IC1") (pin "3") (pinfunction "VO_3") (pintype "passive"))
      (node (ref "IC3") (pin "9") (pinfunction "VDD_9") (pintype "power_in"))
      (node (ref "IC4") (pin "18") (pinfunction "AVCC_18") (pintype "bidirectional"))
      (node (ref "IC4") (pin "4") (pinfunction "VCC_4") (pintype "bidirectional"))
      (node (ref "IC4") (pin "6") (pinfunction "VCC_6") (pintype "bidirectional"))
      (node (ref "IC5") (pin "16") (pinfunction "VCC_16") (pintype "bidirectional"))
      (node (ref "IC6") (pin "1") (pinfunction "VCC_1") (pintype "power_in"))
      (node (ref "IC8") (pin "3") (pinfunction "VDD_3") (pintype "power_in"))
      (node (ref "IC9") (pin "3") (pinfunction "VDD_3") (pintype "power_in"))
      (node (ref "R10") (pin "1") (pinfunction "1_1") (pintype "passive"))
      (node (ref "R17") (pin "1") (pinfunction "1_1") (pintype "passive"))
      (node (ref "R18") (pin "1") (pinfunction "1_1") (pintype "passive"))
      (node (ref "R20") (pin "1") (pinfunction "1_1") (pintype "passive"))
      (node (ref "R7") (pin "1") (pinfunction "1_1") (pintype "passive"))
      (node (ref "U$10") (pin "OUT+") (pinfunction "OUT+_OUT+") (pintype "bidirectional"))
      (node (ref "U$5") (pin "+5V") (pinfunction "5V_+5V") (pintype "bidirectional"))
      (node (ref "U$6") (pin "BLA") (pinfunction "BLA_BLA") (pintype "bidirectional"))
      (node (ref "U$6") (pin "VDD") (pinfunction "VDD_VDD") (pintype "bidirectional"))
    )
    (net (code "79") (name "VLOAD_ATT") (class "Default")
      (node (ref "IC4") (pin "26") (pinfunction "PC3(ADC3)_26") (pintype "bidirectional"))
      (node (ref "R12") (pin "1") (pinfunction "1_1") (pintype "passive"))
      (node (ref "R13") (pin "2") (pinfunction "2_2") (pintype "passive"))
      (node (ref "VLOAD_ATT") (pin "TP") (pinfunction "TP_TP") (pintype "input"))
    )
    (net (code "80") (name "VLOAD_DROP") (class "Default")
      (node (ref "IC2") (pin "6") (pinfunction "-IN_6") (pintype "input"))
      (node (ref "IC4") (pin "25") (pinfunction "PC2(ADC2)_25") (pintype "bidirectional"))
      (node (ref "Q1") (pin "3") (pinfunction "S_3") (pintype "passive"))
      (node (ref "Q3") (pin "3") (pinfunction "S_3") (pintype "passive"))
      (node (ref "R4") (pin "1") (pinfunction "1_1") (pintype "passive"))
      (node (ref "R5") (pin "2") (pinfunction "2_2") (pintype "passive"))
      (node (ref "VLOAD_DROP") (pin "TP") (pinfunction "TP_TP") (pintype "input"))
    )
    (net (code "81") (name "unconnected-(H5-MOUNT-PadB3,0)") (class "Default")
      (node (ref "H5") (pin "B3,0") (pinfunction "MOUNT_B3,0") (pintype "passive"))
    )
    (net (code "82") (name "unconnected-(H6-MOUNT-PadB3,0)") (class "Default")
      (node (ref "H6") (pin "B3,0") (pinfunction "MOUNT_B3,0") (pintype "passive"))
    )
    (net (code "83") (name "unconnected-(IC3-GPA5-Pad26)") (class "Default")
      (node (ref "IC3") (pin "26") (pinfunction "GPA5_26") (pintype "bidirectional"))
    )
    (net (code "84") (name "unconnected-(IC3-GPA6-Pad27)") (class "Default")
      (node (ref "IC3") (pin "27") (pinfunction "GPA6_27") (pintype "bidirectional"))
    )
    (net (code "85") (name "unconnected-(IC3-GPA7-Pad28)") (class "Default")
      (node (ref "IC3") (pin "28") (pinfunction "GPA7_28") (pintype "bidirectional"))
    )
    (net (code "86") (name "unconnected-(IC3-INTA-Pad20)") (class "Default")
      (node (ref "IC3") (pin "20") (pinfunction "INTA_20") (pintype "output"))
    )
    (net (code "87") (name "unconnected-(IC3-INTB-Pad19)") (class "Default")
      (node (ref "IC3") (pin "19") (pinfunction "INTB_19") (pintype "output"))
    )
    (net (code "88") (name "unconnected-(IC4-ADC6-Pad19)") (class "Default")
      (node (ref "IC4") (pin "19") (pinfunction "ADC6_19") (pintype "bidirectional"))
    )
    (net (code "89") (name "unconnected-(IC4-ADC7-Pad22)") (class "Default")
      (node (ref "IC4") (pin "22") (pinfunction "ADC7_22") (pintype "bidirectional"))
    )
    (net (code "90") (name "unconnected-(IC5-T2IN-Pad10)") (class "Default")
      (node (ref "IC5") (pin "10") (pinfunction "T2IN_10") (pintype "input"))
    )
    (net (code "91") (name "unconnected-(IC5-T2OUT-Pad7)") (class "Default")
      (node (ref "IC5") (pin "7") (pinfunction "T2OUT_7") (pintype "output"))
    )
    (net (code "92") (name "unconnected-(JP2-Pad1)") (class "Default")
      (node (ref "JP2") (pin "1") (pinfunction "1_1") (pintype "passive"))
    )
    (net (code "93") (name "unconnected-(JP2-Pad7)") (class "Default")
      (node (ref "JP2") (pin "7") (pinfunction "7_7") (pintype "passive"))
    )
    (net (code "94") (name "unconnected-(JP2-Pad8)") (class "Default")
      (node (ref "JP2") (pin "8") (pinfunction "8_8") (pintype "passive"))
    )
    (net (code "95") (name "unconnected-(JP2-Pad9)") (class "Default")
      (node (ref "JP2") (pin "9") (pinfunction "9_9") (pintype "passive"))
    )
    (net (code "96") (name "unconnected-(KK1-K-PadK1)") (class "Default")
      (node (ref "KK1") (pin "K1") (pinfunction "K_K1") (pintype "passive"))
    )
    (net (code "97") (name "unconnected-(KK1-K-PadK2)") (class "Default")
      (node (ref "KK1") (pin "K2") (pinfunction "K_K2") (pintype "passive"))
    )
    (net (code "98") (name "unconnected-(KK3-K-PadK1)") (class "Default")
      (node (ref "KK3") (pin "K1") (pinfunction "K_K1") (pintype "passive"))
    )
    (net (code "99") (name "unconnected-(KK3-K-PadK2)") (class "Default")
      (node (ref "KK3") (pin "K2") (pinfunction "K_K2") (pintype "passive"))
    )
  )
)
